# Board_Bawah.net
KiCad netlist of a schematic drawn in EAGLE
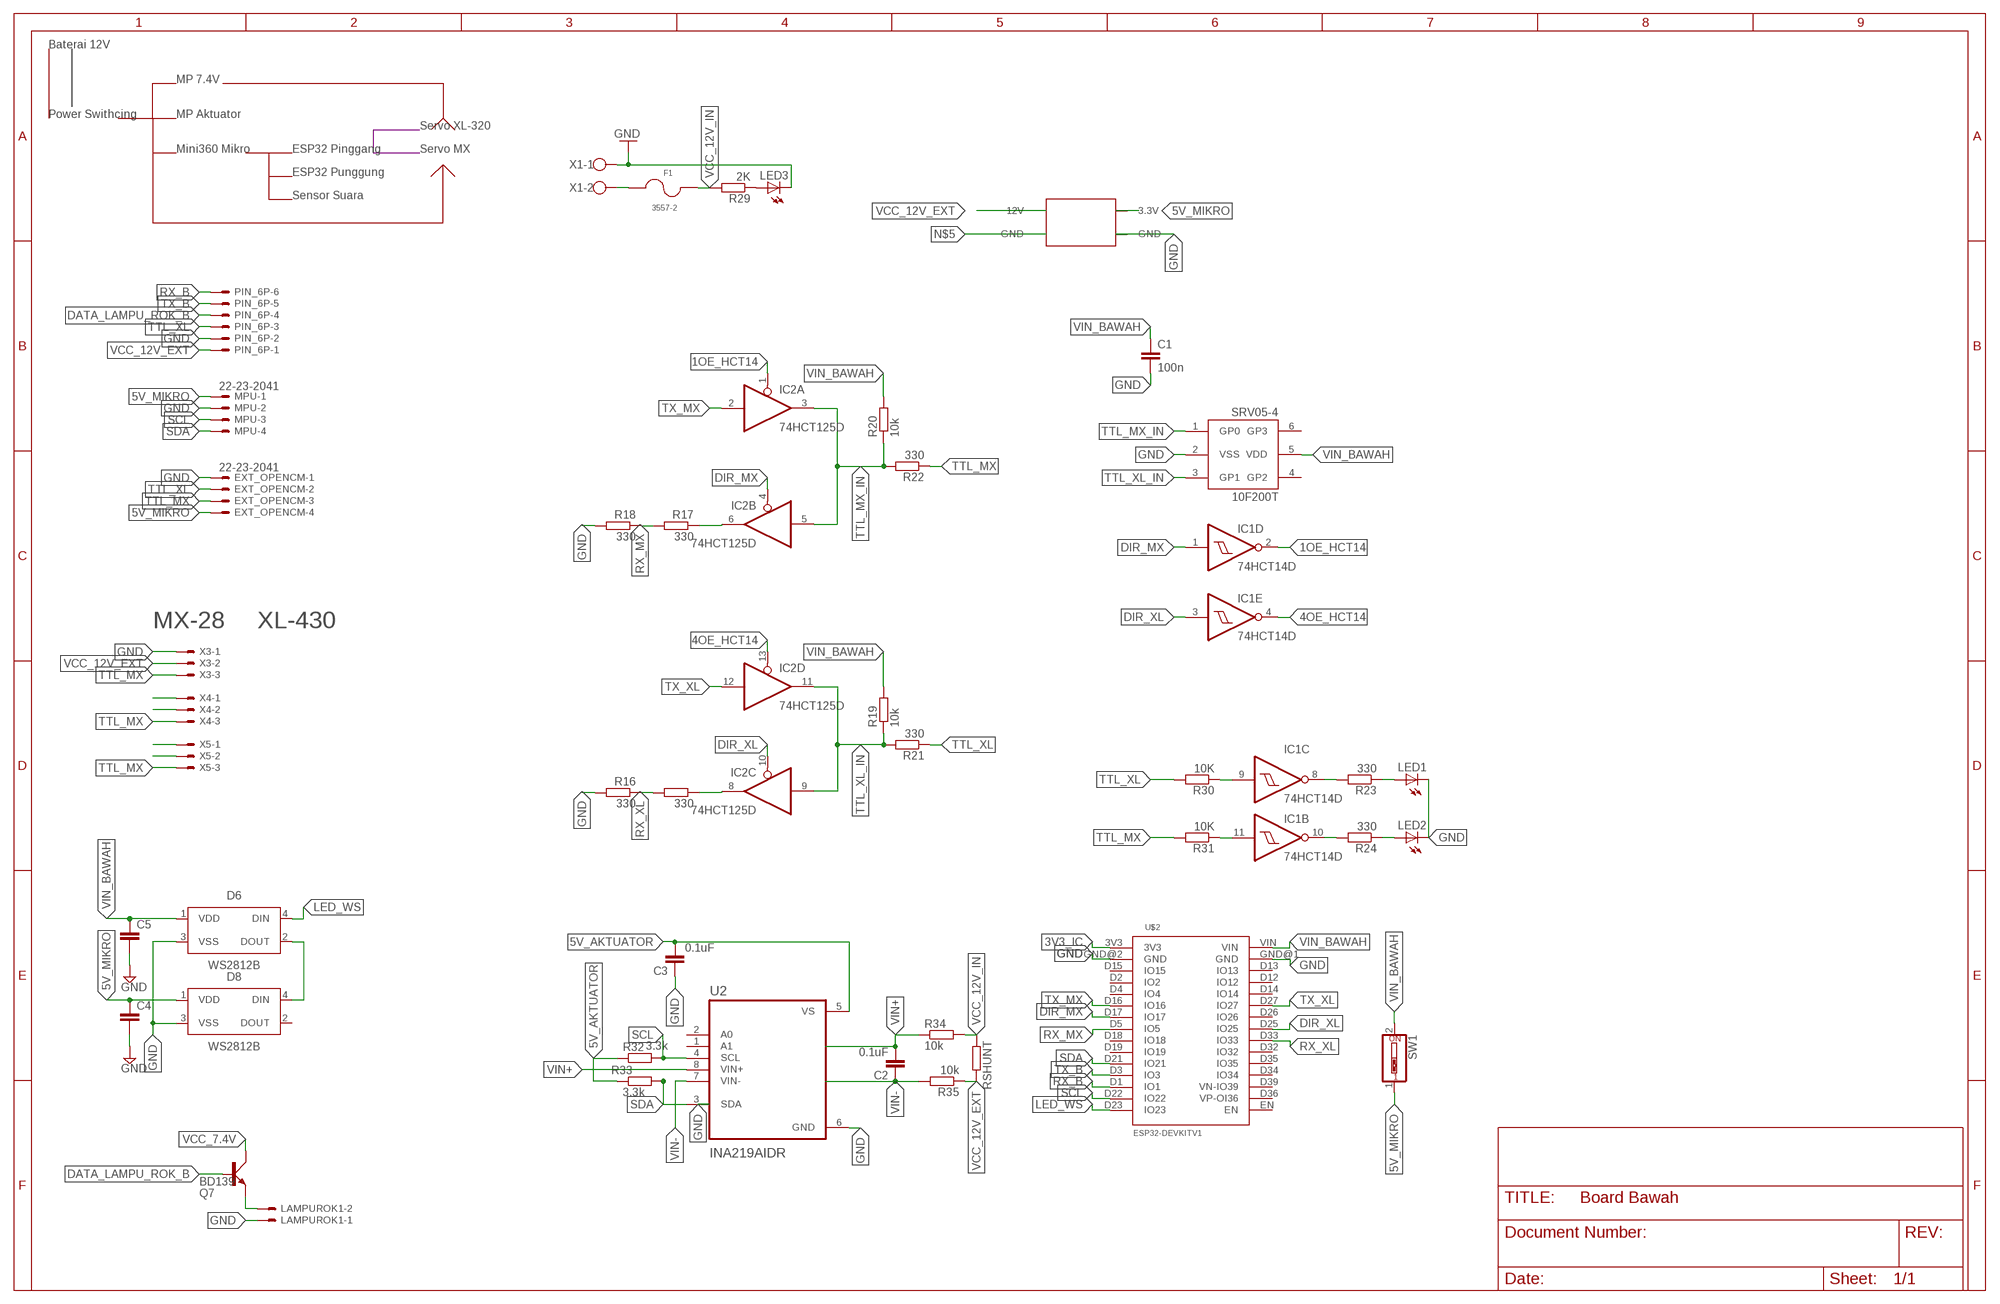
[diagram p0: schematic, sheet 1]

(export (version "E")
  (design (tool "Eeschema 10.0.6"))
  (components
    (comp (ref "C1")
      (value "100n")
      (footprint "eagle-import:C0805")
      (libsource (lib "eagle-import") (part "C-EUC0805"))
    )
    (comp (ref "C2")
      (value "0.1uF")
      (footprint "eagle-import:C0805")
      (libsource (lib "eagle-import") (part "C-EUC0805"))
    )
    (comp (ref "C3")
      (value "0.1uF")
      (footprint "eagle-import:C0805")
      (libsource (lib "eagle-import") (part "C-EUC0805"))
    )
    (comp (ref "C4")
      (value "C-EUC0805")
      (footprint "eagle-import:C0805")
      (libsource (lib "eagle-import") (part "C-EUC0805"))
    )
    (comp (ref "C5")
      (value "C-EUC0805")
      (footprint "eagle-import:C0805")
      (libsource (lib "eagle-import") (part "C-EUC0805"))
    )
    (comp (ref "D6")
      (value "WS2812B")
      (footprint "eagle-import:WS2812B")
      (fields (field (name "MANUFACTURER") "Worldsemi"))
      (libsource (lib "eagle-import") (part "WS2812B"))
    )
    (comp (ref "D8")
      (value "WS2812B")
      (footprint "eagle-import:WS2812B")
      (fields (field (name "MANUFACTURER") "Worldsemi"))
      (libsource (lib "eagle-import") (part "WS2812B"))
    )
    (comp (ref "EXT_OPENCM")
      (value "22-23-2041")
      (footprint "eagle-import:22-23-2041")
      (fields (field (name "MF") "MOLEX"))
      (libsource (lib "eagle-import") (part "22-23-2041"))
    )
    (comp (ref "F1")
      (value "3557-2")
      (footprint "eagle-import:FUSE_3557-2")
      (fields (field (name "MF") "Keystone Electronics"))
      (libsource (lib "eagle-import") (part "3557-2"))
    )
    (comp (ref "IC1")
      (value "74HCT14D")
      (footprint "eagle-import:SO14")
      (fields (field (name "SPICEPREFIX") "I"))
      (libsource (lib "eagle-import") (part "7414DHCT"))
    )
    (comp (ref "IC2")
      (value "74HCT125D")
      (footprint "eagle-import:SO14")
      (libsource (lib "eagle-import") (part "74125DHCT"))
    )
    (comp (ref "LAMPUROK1")
      (value "22-23-2021")
      (footprint "eagle-import:22-23-2021")
      (fields (field (name "MF") "MOLEX"))
      (libsource (lib "eagle-import") (part "22-23-2021"))
    )
    (comp (ref "LED1")
      (value "LEDCHIPLED_1206")
      (footprint "eagle-import:CHIPLED_1206")
      (libsource (lib "eagle-import") (part "LEDCHIPLED_1206"))
    )
    (comp (ref "LED2")
      (value "LEDCHIPLED_1206")
      (footprint "eagle-import:CHIPLED_1206")
      (libsource (lib "eagle-import") (part "LEDCHIPLED_1206"))
    )
    (comp (ref "LED3")
      (value "LEDCHIPLED_1206")
      (footprint "eagle-import:CHIPLED_1206")
      (libsource (lib "eagle-import") (part "LEDCHIPLED_1206"))
    )
    (comp (ref "MPU")
      (value "22-23-2041")
      (footprint "eagle-import:22-23-2041")
      (fields (field (name "MF") "MOLEX"))
      (libsource (lib "eagle-import") (part "22-23-2041"))
    )
    (comp (ref "PIN_6P")
      (value "22-23-2061")
      (footprint "eagle-import:22-23-2061")
      (fields (field (name "MF") "MOLEX"))
      (libsource (lib "eagle-import") (part "22-23-2061"))
    )
    (comp (ref "Q7")
      (value "BD139")
      (footprint "eagle-import:TO126AV")
      (libsource (lib "eagle-import") (part "BD139"))
    )
    (comp (ref "R13")
      (value "330")
      (footprint "eagle-import:R0805")
      (libsource (lib "eagle-import") (part "resistor_348_R-EU_R0805"))
    )
    (comp (ref "R16")
      (value "330")
      (footprint "eagle-import:R0805")
      (libsource (lib "eagle-import") (part "resistor_348_R-EU_R0805"))
    )
    (comp (ref "R17")
      (value "330")
      (footprint "eagle-import:R0805")
      (libsource (lib "eagle-import") (part "resistor_348_R-EU_R0805"))
    )
    (comp (ref "R18")
      (value "330")
      (footprint "eagle-import:R0805")
      (libsource (lib "eagle-import") (part "resistor_348_R-EU_R0805"))
    )
    (comp (ref "R19")
      (value "10k")
      (footprint "eagle-import:R0805")
      (libsource (lib "eagle-import") (part "resistor_348_R-EU_R0805"))
    )
    (comp (ref "R20")
      (value "10k")
      (footprint "eagle-import:R0805")
      (libsource (lib "eagle-import") (part "resistor_348_R-EU_R0805"))
    )
    (comp (ref "R21")
      (value "330")
      (footprint "eagle-import:R0805")
      (libsource (lib "eagle-import") (part "resistor_348_R-EU_R0805"))
    )
    (comp (ref "R22")
      (value "330")
      (footprint "eagle-import:R0805")
      (libsource (lib "eagle-import") (part "resistor_348_R-EU_R0805"))
    )
    (comp (ref "R23")
      (value "330")
      (footprint "eagle-import:R0805")
      (libsource (lib "eagle-import") (part "resistor_348_R-EU_R0805"))
    )
    (comp (ref "R24")
      (value "330")
      (footprint "eagle-import:R0805")
      (libsource (lib "eagle-import") (part "resistor_348_R-EU_R0805"))
    )
    (comp (ref "R29")
      (value "2K")
      (footprint "eagle-import:R0805")
      (libsource (lib "eagle-import") (part "resistor_348_R-EU_R0805"))
    )
    (comp (ref "R30")
      (value "10K")
      (footprint "eagle-import:R0805")
      (libsource (lib "eagle-import") (part "resistor_348_R-EU_R0805"))
    )
    (comp (ref "R31")
      (value "10K")
      (footprint "eagle-import:R0805")
      (libsource (lib "eagle-import") (part "resistor_348_R-EU_R0805"))
    )
    (comp (ref "R32")
      (value "3.3k")
      (footprint "eagle-import:R0805")
      (libsource (lib "eagle-import") (part "resistor_348_R-EU_R0805"))
    )
    (comp (ref "R33")
      (value "3.3k")
      (footprint "eagle-import:R0805")
      (libsource (lib "eagle-import") (part "resistor_348_R-EU_R0805"))
    )
    (comp (ref "R34")
      (value "10k")
      (footprint "eagle-import:R0805")
      (libsource (lib "eagle-import") (part "resistor_348_R-EU_R0805"))
    )
    (comp (ref "R35")
      (value "10k")
      (footprint "eagle-import:R0805")
      (libsource (lib "eagle-import") (part "resistor_348_R-EU_R0805"))
    )
    (comp (ref "RSHUNT")
      (value "R-EU_R2512")
      (footprint "eagle-import:R2512")
      (libsource (lib "eagle-import") (part "R-EU_R2512"))
    )
    (comp (ref "SRV05-4")
      (value "10F200T")
      (footprint "eagle-import:SOT23-6")
      (libsource (lib "eagle-import") (part "10F200T"))
    )
    (comp (ref "SW1")
      (value "SW_DIP-1")
      (footprint "eagle-import:EDG-01")
      (libsource (lib "eagle-import") (part "SW_DIP-1"))
    )
    (comp (ref "U$2")
      (value "ESP32DEVKITV1")
      (footprint "eagle-import:ESP32-DEVKITV1")
      (libsource (lib "eagle-import") (part "ESP32DEVKITV1"))
    )
    (comp (ref "U$5")
      (value "MP2307-MINI-360")
      (footprint "eagle-import:MP2307-MINI-360")
      (libsource (lib "eagle-import") (part "MP2307-MINI-360"))
    )
    (comp (ref "U2")
      (value "INA219AIDR")
      (footprint "eagle-import:SOIC127P599X175-8N")
      (fields (field (name "MF") "Texas Instruments"))
      (libsource (lib "eagle-import") (part "INA219AIDR"))
    )
    (comp (ref "X1")
      (value "W237-102")
      (footprint "eagle-import:W237-102")
      (fields (field (name "MPN") "237-102"))
      (libsource (lib "eagle-import") (part "W237-102"))
    )
    (comp (ref "X3")
      (value "22-23-2031")
      (footprint "eagle-import:22-23-2031")
      (fields (field (name "MF") "MOLEX"))
      (libsource (lib "eagle-import") (part "22-23-2031"))
    )
    (comp (ref "X4")
      (value "22-23-2031")
      (footprint "eagle-import:22-23-2031")
      (fields (field (name "MF") "MOLEX"))
      (libsource (lib "eagle-import") (part "22-23-2031"))
    )
    (comp (ref "X5")
      (value "22-23-2031")
      (footprint "eagle-import:22-23-2031")
      (fields (field (name "MF") "MOLEX"))
      (libsource (lib "eagle-import") (part "22-23-2031"))
    )
  )
  (nets
    (net (code "1") (name "1OE_HCT14") (class "Default")
      (node (ref "IC1") (pin "2") (pinfunction "O_2") (pintype "output"))
      (node (ref "IC2") (pin "1") (pinfunction "OE_1") (pintype "input"))
    )
    (net (code "2") (name "3V3_IC") (class "Default")
      (node (ref "U$2") (pin "3V3") (pinfunction "3V3_3V3") (pintype "bidirectional"))
    )
    (net (code "3") (name "4OE_HCT14") (class "Default")
      (node (ref "IC1") (pin "4") (pinfunction "O_4") (pintype "output"))
      (node (ref "IC2") (pin "13") (pinfunction "OE_13") (pintype "input"))
    )
    (net (code "4") (name "5V_AKTUATOR") (class "Default")
      (node (ref "C3") (pin "2") (pinfunction "2_2") (pintype "passive"))
      (node (ref "R32") (pin "1") (pinfunction "1_1") (pintype "passive"))
      (node (ref "R33") (pin "1") (pinfunction "1_1") (pintype "passive"))
      (node (ref "U2") (pin "5") (pinfunction "VS_5") (pintype "power_in"))
    )
    (net (code "5") (name "5V_MIKRO") (class "Default")
      (node (ref "C4") (pin "1") (pinfunction "1_1") (pintype "passive"))
      (node (ref "D8") (pin "1") (pinfunction "VDD_1") (pintype "power_in"))
      (node (ref "EXT_OPENCM") (pin "4") (pinfunction "S_4") (pintype "passive"))
      (node (ref "MPU") (pin "1") (pinfunction "S_1") (pintype "passive"))
      (node (ref "SW1") (pin "1") (pinfunction "1_1") (pintype "passive"))
      (node (ref "U$5") (pin "V+OUT") (pinfunction "3.3V_V+OUT") (pintype "power_in"))
    )
    (net (code "6") (name "DATA_LAMPU_ROK_B") (class "Default")
      (node (ref "PIN_6P") (pin "4") (pinfunction "S_4") (pintype "passive"))
      (node (ref "Q7") (pin "B") (pinfunction "B_B") (pintype "passive"))
    )
    (net (code "7") (name "DIR_MX") (class "Default")
      (node (ref "IC1") (pin "1") (pinfunction "I_1") (pintype "input"))
      (node (ref "IC2") (pin "4") (pinfunction "OE_4") (pintype "input"))
      (node (ref "U$2") (pin "D17") (pinfunction "IO17_D17") (pintype "bidirectional"))
    )
    (net (code "8") (name "DIR_XL") (class "Default")
      (node (ref "IC1") (pin "3") (pinfunction "I_3") (pintype "input"))
      (node (ref "IC2") (pin "10") (pinfunction "OE_10") (pintype "input"))
      (node (ref "U$2") (pin "D25") (pinfunction "IO25_D25") (pintype "bidirectional"))
    )
    (net (code "9") (name "GND") (class "Default")
      (node (ref "C1") (pin "2") (pinfunction "2_2") (pintype "passive"))
      (node (ref "C3") (pin "1") (pinfunction "1_1") (pintype "passive"))
      (node (ref "C4") (pin "2") (pinfunction "2_2") (pintype "passive"))
      (node (ref "C5") (pin "2") (pinfunction "2_2") (pintype "passive"))
      (node (ref "D6") (pin "3") (pinfunction "VSS_3") (pintype "power_in"))
      (node (ref "D8") (pin "3") (pinfunction "VSS_3") (pintype "power_in"))
      (node (ref "EXT_OPENCM") (pin "1") (pinfunction "S_1") (pintype "passive"))
      (node (ref "LAMPUROK1") (pin "1") (pinfunction "S_1") (pintype "passive"))
      (node (ref "LED1") (pin "C") (pinfunction "C_C") (pintype "passive"))
      (node (ref "LED2") (pin "C") (pinfunction "C_C") (pintype "passive"))
      (node (ref "LED3") (pin "C") (pinfunction "C_C") (pintype "passive"))
      (node (ref "MPU") (pin "2") (pinfunction "S_2") (pintype "passive"))
      (node (ref "PIN_6P") (pin "2") (pinfunction "S_2") (pintype "passive"))
      (node (ref "R16") (pin "2") (pinfunction "2_2") (pintype "passive"))
      (node (ref "R18") (pin "2") (pinfunction "2_2") (pintype "passive"))
      (node (ref "SRV05-4") (pin "2") (pinfunction "VSS_2") (pintype "power_in"))
      (node (ref "U$2") (pin "GND@1") (pinfunction "GND_GND@1") (pintype "bidirectional"))
      (node (ref "U$2") (pin "GND@2") (pinfunction "GND_GND@2") (pintype "bidirectional"))
      (node (ref "U$5") (pin "GND_OUT") (pinfunction "GND_GND_OUT") (pintype "power_in"))
      (node (ref "U2") (pin "6") (pinfunction "GND_6") (pintype "power_in"))
      (node (ref "X1") (pin "1") (pinfunction "KL_1") (pintype "passive"))
      (node (ref "X3") (pin "1") (pinfunction "S_1") (pintype "passive"))
      (node (ref "X4") (pin "1") (pinfunction "S_1") (pintype "passive"))
      (node (ref "X5") (pin "1") (pinfunction "S_1") (pintype "passive"))
    )
    (net (code "10") (name "LED_WS") (class "Default")
      (node (ref "D6") (pin "4") (pinfunction "DIN_4") (pintype "input"))
      (node (ref "U$2") (pin "D23") (pinfunction "IO23_D23") (pintype "bidirectional"))
    )
    (net (code "11") (name "N$5") (class "Default")
      (node (ref "U$5") (pin "GND_IN") (pinfunction "GND_GND_IN") (pintype "power_in"))
    )
    (net (code "12") (name "Net-(D6-DOUT)") (class "Default")
      (node (ref "D6") (pin "2") (pinfunction "DOUT_2") (pintype "output"))
      (node (ref "D8") (pin "4") (pinfunction "DIN_4") (pintype "input"))
    )
    (net (code "13") (name "Net-(IC1B-I)") (class "Default")
      (node (ref "IC1") (pin "11") (pinfunction "I_11") (pintype "input"))
      (node (ref "R31") (pin "1") (pinfunction "1_1") (pintype "passive"))
    )
    (net (code "14") (name "Net-(IC1B-O)") (class "Default")
      (node (ref "IC1") (pin "10") (pinfunction "O_10") (pintype "output"))
      (node (ref "R24") (pin "2") (pinfunction "2_2") (pintype "passive"))
    )
    (net (code "15") (name "Net-(IC1C-I)") (class "Default")
      (node (ref "IC1") (pin "9") (pinfunction "I_9") (pintype "input"))
      (node (ref "R30") (pin "1") (pinfunction "1_1") (pintype "passive"))
    )
    (net (code "16") (name "Net-(IC1C-O)") (class "Default")
      (node (ref "IC1") (pin "8") (pinfunction "O_8") (pintype "output"))
      (node (ref "R23") (pin "2") (pinfunction "2_2") (pintype "passive"))
    )
    (net (code "17") (name "Net-(IC2B-O)") (class "Default")
      (node (ref "IC2") (pin "6") (pinfunction "O_6") (pintype "tri_state"))
      (node (ref "R17") (pin "1") (pinfunction "1_1") (pintype "passive"))
    )
    (net (code "18") (name "Net-(IC2C-O)") (class "Default")
      (node (ref "IC2") (pin "8") (pinfunction "O_8") (pintype "tri_state"))
      (node (ref "R13") (pin "1") (pinfunction "1_1") (pintype "passive"))
    )
    (net (code "19") (name "Net-(LAMPUROK1B-S)") (class "Default")
      (node (ref "LAMPUROK1") (pin "2") (pinfunction "S_2") (pintype "passive"))
      (node (ref "Q7") (pin "E") (pinfunction "E_E") (pintype "passive"))
    )
    (net (code "20") (name "Net-(LED1-PadA)") (class "Default")
      (node (ref "LED1") (pin "A") (pinfunction "A_A") (pintype "passive"))
      (node (ref "R23") (pin "1") (pinfunction "1_1") (pintype "passive"))
    )
    (net (code "21") (name "Net-(LED2-PadA)") (class "Default")
      (node (ref "LED2") (pin "A") (pinfunction "A_A") (pintype "passive"))
      (node (ref "R24") (pin "1") (pinfunction "1_1") (pintype "passive"))
    )
    (net (code "22") (name "Net-(LED3-PadA)") (class "Default")
      (node (ref "LED3") (pin "A") (pinfunction "A_A") (pintype "passive"))
      (node (ref "R29") (pin "1") (pinfunction "1_1") (pintype "passive"))
    )
    (net (code "23") (name "Net-(X1B-KL)") (class "Default")
      (node (ref "F1") (pin "1_1") (pinfunction "1_1_1") (pintype "passive"))
      (node (ref "F1") (pin "1_2") (pinfunction "1_1_2") (pintype "passive"))
      (node (ref "X1") (pin "2") (pinfunction "KL_2") (pintype "passive"))
    )
    (net (code "24") (name "RX_B") (class "Default")
      (node (ref "PIN_6P") (pin "6") (pinfunction "S_6") (pintype "passive"))
      (node (ref "U$2") (pin "D1") (pinfunction "IO1_D1") (pintype "bidirectional"))
    )
    (net (code "25") (name "RX_MX") (class "Default")
      (node (ref "R17") (pin "2") (pinfunction "2_2") (pintype "passive"))
      (node (ref "R18") (pin "1") (pinfunction "1_1") (pintype "passive"))
      (node (ref "U$2") (pin "D5") (pinfunction "IO5_D5") (pintype "bidirectional"))
    )
    (net (code "26") (name "RX_XL") (class "Default")
      (node (ref "R13") (pin "2") (pinfunction "2_2") (pintype "passive"))
      (node (ref "R16") (pin "1") (pinfunction "1_1") (pintype "passive"))
      (node (ref "U$2") (pin "D33") (pinfunction "IO33_D33") (pintype "bidirectional"))
    )
    (net (code "27") (name "SCL") (class "Default")
      (node (ref "MPU") (pin "3") (pinfunction "S_3") (pintype "passive"))
      (node (ref "R32") (pin "2") (pinfunction "2_2") (pintype "passive"))
      (node (ref "U$2") (pin "D22") (pinfunction "IO22_D22") (pintype "bidirectional"))
      (node (ref "U2") (pin "4") (pinfunction "SCL_4") (pintype "input"))
    )
    (net (code "28") (name "SDA") (class "Default")
      (node (ref "MPU") (pin "4") (pinfunction "S_4") (pintype "passive"))
      (node (ref "R33") (pin "2") (pinfunction "2_2") (pintype "passive"))
      (node (ref "U$2") (pin "D21") (pinfunction "IO21_D21") (pintype "bidirectional"))
      (node (ref "U2") (pin "3") (pinfunction "SDA_3") (pintype "bidirectional"))
    )
    (net (code "29") (name "TTL_MX") (class "Default")
      (node (ref "EXT_OPENCM") (pin "3") (pinfunction "S_3") (pintype "passive"))
      (node (ref "R22") (pin "1") (pinfunction "1_1") (pintype "passive"))
      (node (ref "R31") (pin "2") (pinfunction "2_2") (pintype "passive"))
      (node (ref "X3") (pin "3") (pinfunction "S_3") (pintype "passive"))
      (node (ref "X4") (pin "3") (pinfunction "S_3") (pintype "passive"))
      (node (ref "X5") (pin "3") (pinfunction "S_3") (pintype "passive"))
    )
    (net (code "30") (name "TTL_MX_IN") (class "Default")
      (node (ref "IC2") (pin "3") (pinfunction "O_3") (pintype "tri_state"))
      (node (ref "IC2") (pin "5") (pinfunction "I_5") (pintype "input"))
      (node (ref "R20") (pin "1") (pinfunction "1_1") (pintype "passive"))
      (node (ref "R22") (pin "2") (pinfunction "2_2") (pintype "passive"))
      (node (ref "SRV05-4") (pin "1") (pinfunction "GP0_1") (pintype "bidirectional"))
    )
    (net (code "31") (name "TTL_XL") (class "Default")
      (node (ref "EXT_OPENCM") (pin "2") (pinfunction "S_2") (pintype "passive"))
      (node (ref "PIN_6P") (pin "3") (pinfunction "S_3") (pintype "passive"))
      (node (ref "R21") (pin "1") (pinfunction "1_1") (pintype "passive"))
      (node (ref "R30") (pin "2") (pinfunction "2_2") (pintype "passive"))
    )
    (net (code "32") (name "TTL_XL_IN") (class "Default")
      (node (ref "IC2") (pin "11") (pinfunction "O_11") (pintype "tri_state"))
      (node (ref "IC2") (pin "9") (pinfunction "I_9") (pintype "input"))
      (node (ref "R19") (pin "1") (pinfunction "1_1") (pintype "passive"))
      (node (ref "R21") (pin "2") (pinfunction "2_2") (pintype "passive"))
      (node (ref "SRV05-4") (pin "3") (pinfunction "GP1_3") (pintype "bidirectional"))
    )
    (net (code "33") (name "TX_B") (class "Default")
      (node (ref "PIN_6P") (pin "5") (pinfunction "S_5") (pintype "passive"))
      (node (ref "U$2") (pin "D3") (pinfunction "IO3_D3") (pintype "bidirectional"))
    )
    (net (code "34") (name "TX_MX") (class "Default")
      (node (ref "IC2") (pin "2") (pinfunction "I_2") (pintype "input"))
      (node (ref "U$2") (pin "D16") (pinfunction "IO16_D16") (pintype "bidirectional"))
    )
    (net (code "35") (name "TX_XL") (class "Default")
      (node (ref "IC2") (pin "12") (pinfunction "I_12") (pintype "input"))
      (node (ref "U$2") (pin "D27") (pinfunction "IO27_D27") (pintype "bidirectional"))
    )
    (net (code "36") (name "VCC_7.4V") (class "Default")
      (node (ref "Q7") (pin "C") (pinfunction "C_C") (pintype "passive"))
    )
    (net (code "37") (name "VCC_12V_EXT") (class "Default")
      (node (ref "PIN_6P") (pin "1") (pinfunction "S_1") (pintype "passive"))
      (node (ref "R35") (pin "1") (pinfunction "1_1") (pintype "passive"))
      (node (ref "RSHUNT") (pin "2") (pinfunction "2_2") (pintype "passive"))
      (node (ref "U$5") (pin "V+IN") (pinfunction "12V_V+IN") (pintype "power_in"))
      (node (ref "X3") (pin "2") (pinfunction "S_2") (pintype "passive"))
      (node (ref "X4") (pin "2") (pinfunction "S_2") (pintype "passive"))
      (node (ref "X5") (pin "2") (pinfunction "S_2") (pintype "passive"))
    )
    (net (code "38") (name "VCC_12V_IN") (class "Default")
      (node (ref "F1") (pin "2_1") (pinfunction "2_2_1") (pintype "passive"))
      (node (ref "F1") (pin "2_2") (pinfunction "2_2_2") (pintype "passive"))
      (node (ref "R29") (pin "2") (pinfunction "2_2") (pintype "passive"))
      (node (ref "R34") (pin "2") (pinfunction "2_2") (pintype "passive"))
      (node (ref "RSHUNT") (pin "1") (pinfunction "1_1") (pintype "passive"))
    )
    (net (code "39") (name "VIN+") (class "Default")
      (node (ref "C2") (pin "2") (pinfunction "2_2") (pintype "passive"))
      (node (ref "R34") (pin "1") (pinfunction "1_1") (pintype "passive"))
      (node (ref "U2") (pin "8") (pinfunction "VIN+_8") (pintype "input"))
    )
    (net (code "40") (name "VIN-") (class "Default")
      (node (ref "C2") (pin "1") (pinfunction "1_1") (pintype "passive"))
      (node (ref "R35") (pin "2") (pinfunction "2_2") (pintype "passive"))
      (node (ref "U2") (pin "7") (pinfunction "VIN-_7") (pintype "input"))
    )
    (net (code "41") (name "VIN_BAWAH") (class "Default")
      (node (ref "C1") (pin "1") (pinfunction "1_1") (pintype "passive"))
      (node (ref "C5") (pin "1") (pinfunction "1_1") (pintype "passive"))
      (node (ref "D6") (pin "1") (pinfunction "VDD_1") (pintype "power_in"))
      (node (ref "R19") (pin "2") (pinfunction "2_2") (pintype "passive"))
      (node (ref "R20") (pin "2") (pinfunction "2_2") (pintype "passive"))
      (node (ref "SRV05-4") (pin "5") (pinfunction "VDD_5") (pintype "power_in"))
      (node (ref "SW1") (pin "2") (pinfunction "2_2") (pintype "passive"))
      (node (ref "U$2") (pin "VIN") (pinfunction "VIN_VIN") (pintype "bidirectional"))
    )
    (net (code "42") (name "unconnected-(D8-DOUT-Pad2)") (class "Default")
      (node (ref "D8") (pin "2") (pinfunction "DOUT_2") (pintype "output"))
    )
    (net (code "43") (name "unconnected-(SRV05-4-GP2-Pad4)") (class "Default")
      (node (ref "SRV05-4") (pin "4") (pinfunction "GP2_4") (pintype "bidirectional"))
    )
    (net (code "44") (name "unconnected-(SRV05-4-GP3-Pad6)") (class "Default")
      (node (ref "SRV05-4") (pin "6") (pinfunction "GP3_6") (pintype "bidirectional"))
    )
    (net (code "45") (name "unconnected-(U$2-IO2-PadD2)") (class "Default")
      (node (ref "U$2") (pin "D2") (pinfunction "IO2_D2") (pintype "bidirectional"))
    )
    (net (code "46") (name "unconnected-(U$2-IO4-PadD4)") (class "Default")
      (node (ref "U$2") (pin "D4") (pinfunction "IO4_D4") (pintype "bidirectional"))
    )
    (net (code "47") (name "unconnected-(U$2-IO12-PadD12)") (class "Default")
      (node (ref "U$2") (pin "D12") (pinfunction "IO12_D12") (pintype "bidirectional"))
    )
    (net (code "48") (name "unconnected-(U$2-IO13-PadD13)") (class "Default")
      (node (ref "U$2") (pin "D13") (pinfunction "IO13_D13") (pintype "bidirectional"))
    )
    (net (code "49") (name "unconnected-(U$2-IO14-PadD14)") (class "Default")
      (node (ref "U$2") (pin "D14") (pinfunction "IO14_D14") (pintype "bidirectional"))
    )
    (net (code "50") (name "unconnected-(U$2-IO15-PadD15)") (class "Default")
      (node (ref "U$2") (pin "D15") (pinfunction "IO15_D15") (pintype "bidirectional"))
    )
    (net (code "51") (name "unconnected-(U$2-IO18-PadD18)") (class "Default")
      (node (ref "U$2") (pin "D18") (pinfunction "IO18_D18") (pintype "bidirectional"))
    )
    (net (code "52") (name "unconnected-(U$2-IO19-PadD19)") (class "Default")
      (node (ref "U$2") (pin "D19") (pinfunction "IO19_D19") (pintype "bidirectional"))
    )
    (net (code "53") (name "unconnected-(U$2-IO26-PadD26)") (class "Default")
      (node (ref "U$2") (pin "D26") (pinfunction "IO26_D26") (pintype "bidirectional"))
    )
    (net (code "54") (name "unconnected-(U$2-IO32-PadD32)") (class "Default")
      (node (ref "U$2") (pin "D32") (pinfunction "IO32_D32") (pintype "bidirectional"))
    )
    (net (code "55") (name "unconnected-(U$2-IO34-PadD34)") (class "Default")
      (node (ref "U$2") (pin "D34") (pinfunction "IO34_D34") (pintype "bidirectional"))
    )
    (net (code "56") (name "unconnected-(U$2-IO35-PadD35)") (class "Default")
      (node (ref "U$2") (pin "D35") (pinfunction "IO35_D35") (pintype "bidirectional"))
    )
    (net (code "57") (name "unconnected-(U$2-PadEN)") (class "Default")
      (node (ref "U$2") (pin "EN") (pinfunction "EN_EN") (pintype "bidirectional"))
    )
    (net (code "58") (name "unconnected-(U$2-VN-IO39-PadD39)") (class "Default")
      (node (ref "U$2") (pin "D39") (pinfunction "VN-IO39_D39") (pintype "bidirectional"))
    )
    (net (code "59") (name "unconnected-(U$2-VP-OI36-PadD36)") (class "Default")
      (node (ref "U$2") (pin "D36") (pinfunction "VP-OI36_D36") (pintype "bidirectional"))
    )
    (net (code "60") (name "unconnected-(U2-A0-Pad2)") (class "Default")
      (node (ref "U2") (pin "2") (pinfunction "A0_2") (pintype "input"))
    )
    (net (code "61") (name "unconnected-(U2-A1-Pad1)") (class "Default")
      (node (ref "U2") (pin "1") (pinfunction "A1_1") (pintype "input"))
    )
  )
)
